# LED-Driver.net
KiCad netlist of a schematic drawn in EAGLE
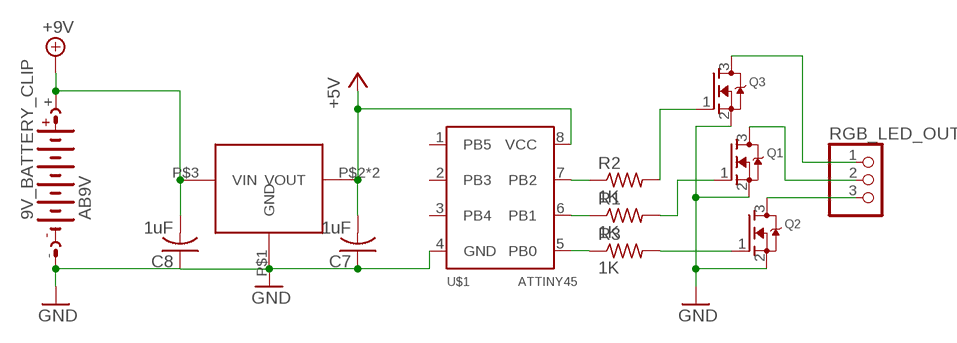
[diagram p0: schematic, sheet 1]

(export (version "E")
  (design (tool "Eeschema 10.0.6"))
  (components
    (comp (ref "5V_LDO")
      (value "5V_LDO")
      (footprint "eagle-import:SOT-223")
      (libsource (lib "eagle-import") (part "5V_LDO"))
    )
    (comp (ref "9V_BATTERY_CLIP")
      (value "AB9V")
      (footprint "eagle-import:AB9V")
      (libsource (lib "eagle-import") (part "AB9V"))
    )
    (comp (ref "C7")
      (value "1uF")
      (footprint "eagle-import:C0805")
      (libsource (lib "eagle-import") (part "C-USC0805"))
    )
    (comp (ref "C8")
      (value "1uF")
      (footprint "eagle-import:C0805")
      (libsource (lib "eagle-import") (part "C-USC0805"))
    )
    (comp (ref "Q1")
      (value "MOSFET-NREFLOW")
      (footprint "eagle-import:SOT23")
      (libsource (lib "eagle-import") (part "MOSFET-NREFLOW"))
    )
    (comp (ref "Q2")
      (value "MOSFET-NREFLOW")
      (footprint "eagle-import:SOT23")
      (libsource (lib "eagle-import") (part "MOSFET-NREFLOW"))
    )
    (comp (ref "Q3")
      (value "MOSFET-NREFLOW")
      (footprint "eagle-import:SOT23")
      (libsource (lib "eagle-import") (part "MOSFET-NREFLOW"))
    )
    (comp (ref "R1")
      (value "1K")
      (footprint "eagle-import:R0805")
      (libsource (lib "eagle-import") (part "R-US_R0805"))
    )
    (comp (ref "R2")
      (value "1K")
      (footprint "eagle-import:R0805")
      (libsource (lib "eagle-import") (part "R-US_R0805"))
    )
    (comp (ref "R3")
      (value "1K")
      (footprint "eagle-import:R0805")
      (libsource (lib "eagle-import") (part "R-US_R0805"))
    )
    (comp (ref "RGB_LED_OUT")
      (value "PINHD-1X3")
      (footprint "eagle-import:1X03")
      (libsource (lib "eagle-import") (part "PINHD-1X3"))
    )
    (comp (ref "U$1")
      (value "ATTINY45")
      (footprint "eagle-import:SOIC8")
      (libsource (lib "eagle-import") (part "ATTINY45"))
    )
  )
  (nets
    (net (code "1") (name "+5V") (class "Default")
      (node (ref "5V_LDO") (pin "P$2") (pinfunction "VOUT_P$2") (pintype "bidirectional"))
      (node (ref "5V_LDO") (pin "P$4") (pinfunction "VOUT_P$4") (pintype "bidirectional"))
      (node (ref "C7") (pin "2") (pinfunction "2_2") (pintype "passive"))
      (node (ref "U$1") (pin "8") (pinfunction "VCC_8") (pintype "power_in"))
    )
    (net (code "2") (name "+9V") (class "Default")
      (node (ref "5V_LDO") (pin "P$3") (pinfunction "VIN_P$3") (pintype "bidirectional"))
      (node (ref "9V_BATTERY_CLIP") (pin "+") (pinfunction "+_+") (pintype "passive"))
      (node (ref "C8") (pin "2") (pinfunction "2_2") (pintype "passive"))
    )
    (net (code "3") (name "GND") (class "Default")
      (node (ref "5V_LDO") (pin "P$1") (pinfunction "GND_P$1") (pintype "bidirectional"))
      (node (ref "9V_BATTERY_CLIP") (pin "-") (pinfunction "-_-") (pintype "passive"))
      (node (ref "C7") (pin "1") (pinfunction "1_1") (pintype "passive"))
      (node (ref "C8") (pin "1") (pinfunction "1_1") (pintype "passive"))
      (node (ref "Q1") (pin "2") (pinfunction "S_2") (pintype "bidirectional"))
      (node (ref "Q2") (pin "2") (pinfunction "S_2") (pintype "bidirectional"))
      (node (ref "Q3") (pin "2") (pinfunction "S_2") (pintype "bidirectional"))
      (node (ref "U$1") (pin "4") (pinfunction "GND_4") (pintype "power_in"))
    )
    (net (code "4") (name "Net-(Q1-D)") (class "Default")
      (node (ref "Q1") (pin "3") (pinfunction "D_3") (pintype "bidirectional"))
      (node (ref "RGB_LED_OUT") (pin "2") (pinfunction "2_2") (pintype "passive"))
    )
    (net (code "5") (name "Net-(Q1-G)") (class "Default")
      (node (ref "Q1") (pin "1") (pinfunction "G_1") (pintype "bidirectional"))
      (node (ref "R1") (pin "2") (pinfunction "2_2") (pintype "passive"))
    )
    (net (code "6") (name "Net-(Q2-D)") (class "Default")
      (node (ref "Q2") (pin "3") (pinfunction "D_3") (pintype "bidirectional"))
      (node (ref "RGB_LED_OUT") (pin "3") (pinfunction "3_3") (pintype "passive"))
    )
    (net (code "7") (name "Net-(Q2-G)") (class "Default")
      (node (ref "Q2") (pin "1") (pinfunction "G_1") (pintype "bidirectional"))
      (node (ref "R3") (pin "2") (pinfunction "2_2") (pintype "passive"))
    )
    (net (code "8") (name "Net-(Q3-D)") (class "Default")
      (node (ref "Q3") (pin "3") (pinfunction "D_3") (pintype "bidirectional"))
      (node (ref "RGB_LED_OUT") (pin "1") (pinfunction "1_1") (pintype "passive"))
    )
    (net (code "9") (name "Net-(Q3-G)") (class "Default")
      (node (ref "Q3") (pin "1") (pinfunction "G_1") (pintype "bidirectional"))
      (node (ref "R2") (pin "2") (pinfunction "2_2") (pintype "passive"))
    )
    (net (code "10") (name "Net-(U$1-PB0)") (class "Default")
      (node (ref "R3") (pin "1") (pinfunction "1_1") (pintype "passive"))
      (node (ref "U$1") (pin "5") (pinfunction "PB0_5") (pintype "bidirectional"))
    )
    (net (code "11") (name "Net-(U$1-PB1)") (class "Default")
      (node (ref "R1") (pin "1") (pinfunction "1_1") (pintype "passive"))
      (node (ref "U$1") (pin "6") (pinfunction "PB1_6") (pintype "bidirectional"))
    )
    (net (code "12") (name "Net-(U$1-PB2)") (class "Default")
      (node (ref "R2") (pin "1") (pinfunction "1_1") (pintype "passive"))
      (node (ref "U$1") (pin "7") (pinfunction "PB2_7") (pintype "bidirectional"))
    )
    (net (code "13") (name "unconnected-(U$1-PB3-Pad2)") (class "Default")
      (node (ref "U$1") (pin "2") (pinfunction "PB3_2") (pintype "bidirectional"))
    )
    (net (code "14") (name "unconnected-(U$1-PB4-Pad3)") (class "Default")
      (node (ref "U$1") (pin "3") (pinfunction "PB4_3") (pintype "bidirectional"))
    )
    (net (code "15") (name "unconnected-(U$1-PB5-Pad1)") (class "Default")
      (node (ref "U$1") (pin "1") (pinfunction "PB5_1") (pintype "bidirectional"))
    )
  )
)
